# CH32L103-WUI-R1.net
KiCad netlist of a schematic drawn in Altium Designer
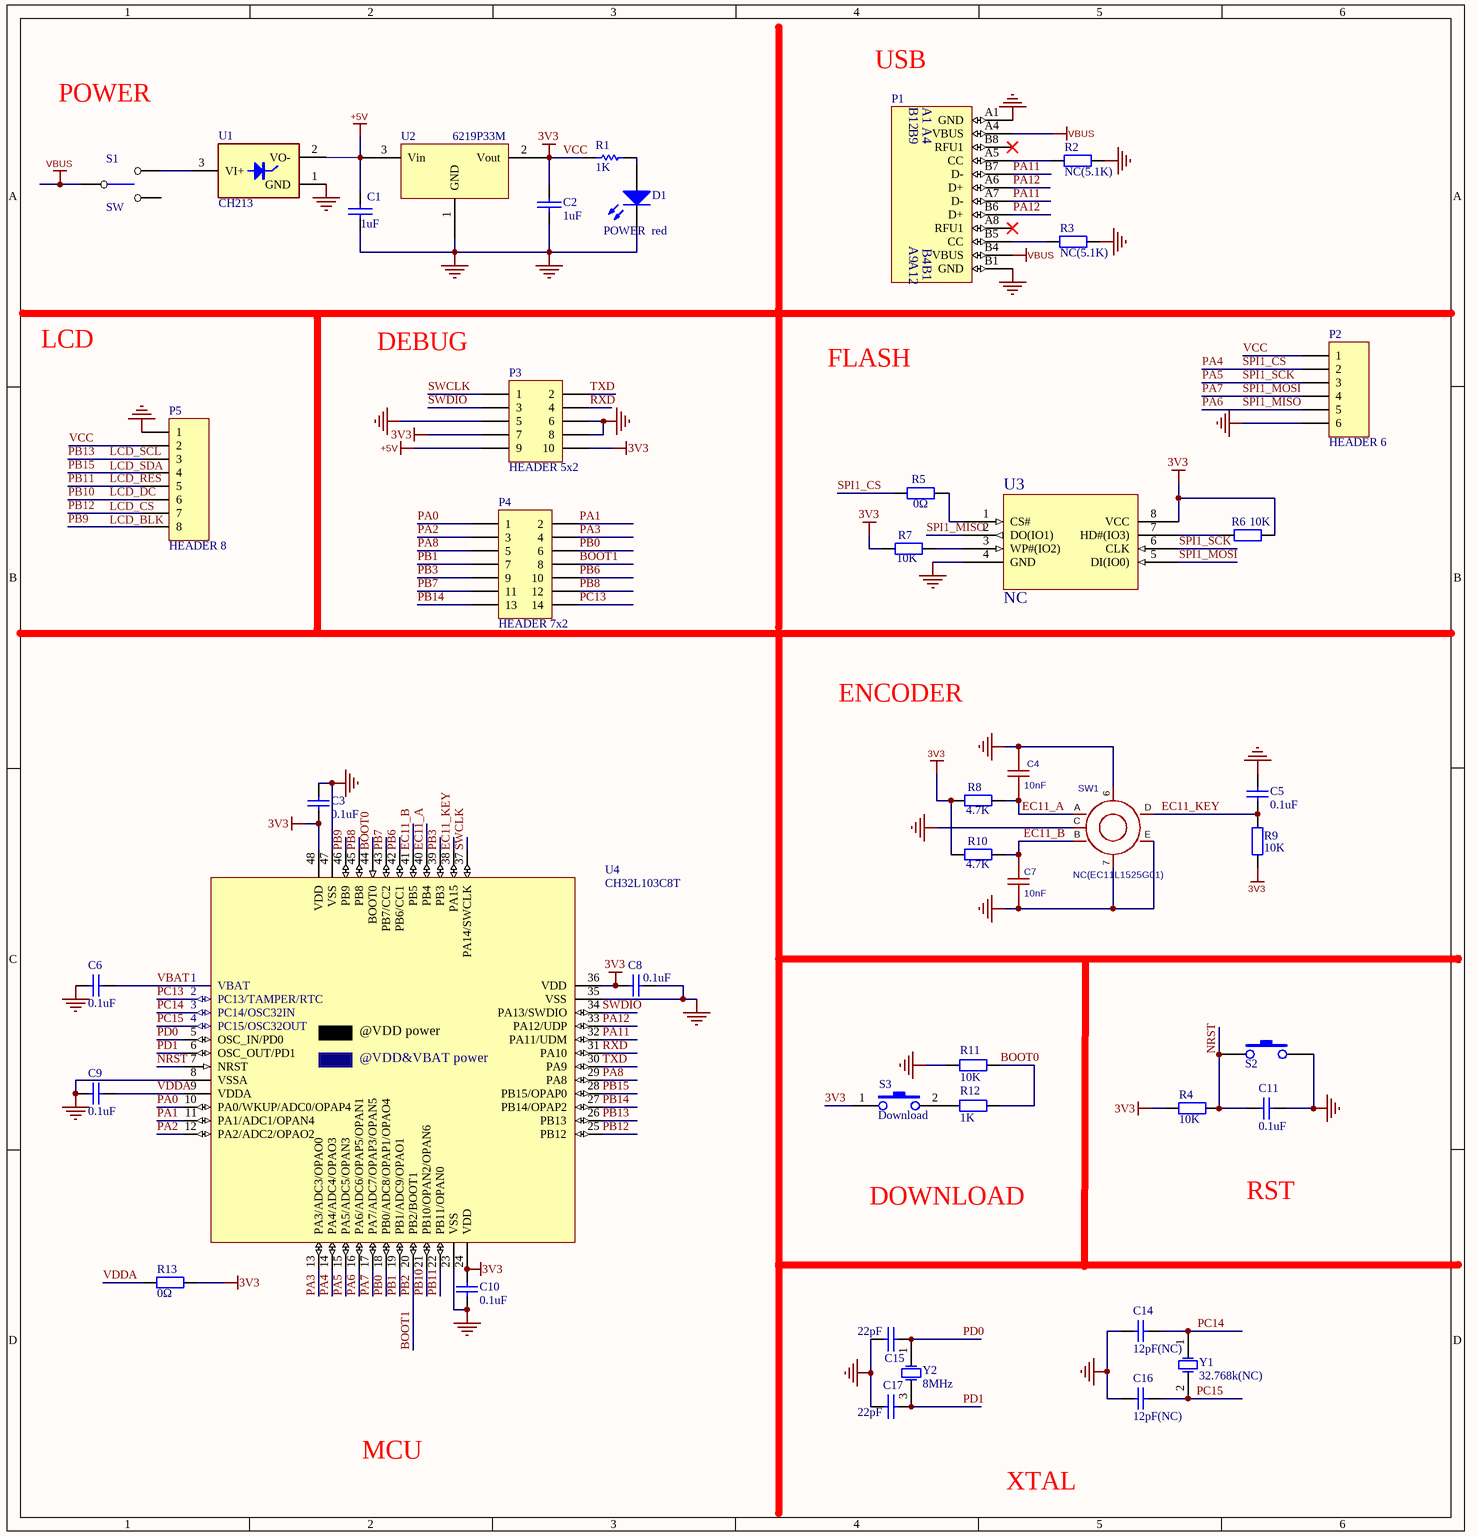
[diagram p0: CH32L103-WUI-R1.SchDoc]

(export (version "E")
  (design (tool "Eeschema 10.0.6"))
  (components
    (comp (ref "C1")
      (value "1uF")
      (footprint "0402_C")
      (description "Capacitor")
      (libsource (lib "*") (part "CAP"))
    )
    (comp (ref "C2")
      (value "1uF")
      (footprint "0402_C")
      (description "Capacitor")
      (libsource (lib "*") (part "CAP"))
    )
    (comp (ref "C3")
      (value "0.1uF")
      (footprint "0402_C")
      (description "Capacitor")
      (fields (field (name "PUBLISHER") "Altium Limited"))
      (libsource (lib "*") (part "Cap"))
    )
    (comp (ref "C4")
      (value "10nF")
      (footprint "0402_C")
      (libsource (lib "altium-import") (part "root_1_CAP_0603_"))
    )
    (comp (ref "C5")
      (value "0.1uF")
      (footprint "0402_C")
      (description "Capacitor")
      (fields (field (name "PUBLISHER") "Altium Limited"))
      (libsource (lib "*") (part "Cap"))
    )
    (comp (ref "C6")
      (value "0.1uF")
      (footprint "0402_C")
      (description "Capacitor")
      (fields (field (name "PUBLISHER") "Altium Limited"))
      (libsource (lib "*") (part "Cap"))
    )
    (comp (ref "C7")
      (value "10nF")
      (footprint "0402_C")
      (libsource (lib "altium-import") (part "root_3_CAP_0603_"))
    )
    (comp (ref "C8")
      (value "0.1uF")
      (footprint "0402_C")
      (description "Capacitor")
      (fields (field (name "PUBLISHER") "Altium Limited"))
      (libsource (lib "*") (part "Cap"))
    )
    (comp (ref "C9")
      (value "0.1uF")
      (footprint "0402_C")
      (description "Capacitor")
      (fields (field (name "PUBLISHER") "Altium Limited"))
      (libsource (lib "*") (part "Cap"))
    )
    (comp (ref "C10")
      (value "0.1uF")
      (footprint "0402_C")
      (description "Capacitor")
      (fields (field (name "PUBLISHER") "Altium Limited"))
      (libsource (lib "*") (part "Cap"))
    )
    (comp (ref "C11")
      (value "0.1uF")
      (footprint "0402_C")
      (description "Capacitor")
      (fields (field (name "PUBLISHER") "Altium Limited"))
      (libsource (lib "*") (part "Cap"))
    )
    (comp (ref "C14")
      (value "12pF(NC)")
      (footprint "0402_C")
      (description "Capacitor")
      (fields (field (name "PUBLISHER") "Altium Limited"))
      (libsource (lib "*") (part "Cap"))
    )
    (comp (ref "C15")
      (value "22pF")
      (footprint "0402_C")
      (description "Capacitor")
      (libsource (lib "*") (part "CAP"))
    )
    (comp (ref "C16")
      (value "12pF(NC)")
      (footprint "0402_C")
      (description "Capacitor")
      (fields (field (name "PUBLISHER") "Altium Limited"))
      (libsource (lib "*") (part "Cap"))
    )
    (comp (ref "C17")
      (value "22pF")
      (footprint "0402_C")
      (description "Capacitor")
      (libsource (lib "*") (part "CAP"))
    )
    (comp (ref "D1")
      (value "POWER  red")
      (footprint "0603+")
      (description "Typical INFRARED GaAs LED")
      (fields (field (name "PUBLISHER") "Altium Limited"))
      (libsource (lib "*") (part "LED0"))
    )
    (comp (ref "P1")
      (value "TYPE-C")
      (footprint "TYPE-C-Receptacle-2.0")
      (libsource (lib "*") (part "TYPE-C1"))
    )
    (comp (ref "P2")
      (value "HEADER 6")
      (footprint "SIP6-2.54mm")
      (description "Header, 6-Pin")
      (libsource (lib "wch_sch_others") (part "HEADER 6"))
    )
    (comp (ref "P3")
      (value "HEADER 5x2")
      (footprint "MYPCB:IDC10-2.54mm")
      (description "Header, 5-Pin, Dual row")
      (libsource (lib "wch_sch_others") (part "HEADER 5x2"))
    )
    (comp (ref "P4")
      (value "HEADER 7x2")
      (footprint "MYPCB:IDC14-2.54mm")
      (description "Header, 7-Pin, Dual row")
      (libsource (lib "wch_sch_others") (part "HEADER 7x2"))
    )
    (comp (ref "P5")
      (value "HEADER 8")
      (footprint "SIP8-2.54mm")
      (description "Header, 8-Pin")
      (libsource (lib "wch_sch_others") (part "HEADER 8"))
    )
    (comp (ref "R1")
      (value "1K")
      (footprint "0402")
      (description "Semiconductor Resistor")
      (fields (field (name "PUBLISHER") "Altium Limited"))
      (libsource (lib "*") (part "Res Semi"))
    )
    (comp (ref "R2")
      (value "NC(5.1K)")
      (footprint "0402")
      (description "Resistor")
      (libsource (lib "Miscellaneous Devices") (part "Res2"))
    )
    (comp (ref "R3")
      (value "NC(5.1K)")
      (footprint "0402")
      (description "Resistor")
      (libsource (lib "Miscellaneous Devices") (part "Res2"))
    )
    (comp (ref "R4")
      (value "10K")
      (footprint "0402")
      (description "Resistor")
      (fields (field (name "PUBLISHER") "Altium Limited"))
      (libsource (lib "") (part "Res2_1"))
    )
    (comp (ref "R5")
      (value "0Ω")
      (footprint "0402")
      (description "Resistor")
      (fields (field (name "PUBLISHER") "Altium Limited"))
      (libsource (lib "*") (part "Res2"))
    )
    (comp (ref "R6")
      (value "10K")
      (footprint "0402")
      (description "Resistor")
      (fields (field (name "PUBLISHER") "Altium Limited"))
      (libsource (lib "*") (part "Res2"))
    )
    (comp (ref "R7")
      (value "10K")
      (footprint "0402")
      (description "Resistor")
      (fields (field (name "PUBLISHER") "Altium Limited"))
      (libsource (lib "*") (part "Res2"))
    )
    (comp (ref "R8")
      (value "4.7K")
      (footprint "0402")
      (description "Resistor")
      (fields (field (name "PUBLISHER") "Altium Limited"))
      (libsource (lib "*") (part "Res2"))
    )
    (comp (ref "R9")
      (value "10K")
      (footprint "0402")
      (description "Resistor")
      (fields (field (name "PUBLISHER") "Altium Limited"))
      (libsource (lib "") (part "Res2_2"))
    )
    (comp (ref "R10")
      (value "4.7K")
      (footprint "0402")
      (description "Resistor")
      (fields (field (name "PUBLISHER") "Altium Limited"))
      (libsource (lib "*") (part "Res2"))
    )
    (comp (ref "R11")
      (value "10K")
      (footprint "0402")
      (description "Resistor")
      (fields (field (name "PUBLISHER") "Altium Limited"))
      (libsource (lib "") (part "Res2_1"))
    )
    (comp (ref "R12")
      (value "1K")
      (footprint "0402")
      (description "Resistor")
      (fields (field (name "PUBLISHER") "Altium Limited"))
      (libsource (lib "") (part "Res2_1"))
    )
    (comp (ref "R13")
      (value "0Ω")
      (footprint "0402")
      (description "Resistor")
      (fields (field (name "PUBLISHER") "Altium Limited"))
      (libsource (lib "") (part "Res2_1"))
    )
    (comp (ref "S1") (value "SW") (footprint "SW1") (libsource (lib "*") (part "SW")))
    (comp (ref "S2") (value "NRST") (footprint "贴片按键") (libsource (lib "*") (part "KEY")))
    (comp (ref "S3") (value "Download") (footprint "贴片按键") (libsource (lib "wch_sch_others") (part "KEY1")))
    (comp (ref "SW1")
      (value "NC(EC11L1525G01)")
      (footprint "SW-TH_ALPS_EC11L1525G01")
      (fields
        (field (name "MANUFACTURER") "ALPSALPINE(阿尔卑斯阿尔派)")
        (field (name "MANUFACTURERPART") "EC11L1525G01")
      )
      (libsource (lib "altium-import") (part "root_3_EC11L1525G01_"))
    )
    (comp (ref "U1")
      (value "CH213")
      (footprint "SOT-23-3")
      (description "Ideal Diode 5V*1A")
      (libsource (lib "CHXXX") (part "CH213E"))
    )
    (comp (ref "U2")
      (value "6219P33M")
      (footprint "SOT-23")
      (libsource (lib "wch_sch_others") (part "6219P33M"))
    )
    (comp (ref "U3")
      (value "NC")
      (footprint "SOIC-8_208mil")
      (libsource (lib "wch_sch_others") (part "W25Q32JV"))
    )
    (comp (ref "U4")
      (value "CH32L103C8T")
      (footprint "LQFP48")
      (description "RISC-V LMD-MCU, 96MHz, USB, Type-C/PD, CAN, OPA, lower power")
      (libsource (lib "CHXXX") (part "CH32L103C8T"))
    )
    (comp (ref "Y1")
      (value "32.768k(NC)")
      (footprint "FC-135")
      (description "Crystal Oscillator")
      (fields (field (name "PUBLISHER") "Altium Limited"))
      (libsource (lib "") (part "XTAL_1"))
    )
    (comp (ref "Y2")
      (value "8MHz")
      (footprint "XT3225")
      (description "Crystal Oscillator")
      (fields (field (name "PUBLISHER") "Altium Limited"))
      (libsource (lib "*") (part "XTAL"))
    )
  )
  (nets
    (net (code "1") (name "+5V") (class "Default")
      (node (ref "C1") (pin "1") (pinfunction "1_1") (pintype "passive"))
      (node (ref "P3") (pin "9") (pinfunction "9_9") (pintype "passive"))
      (node (ref "U1") (pin "2") (pinfunction "VO-_2") (pintype "power_in"))
      (node (ref "U2") (pin "3") (pinfunction "Vin_3") (pintype "passive"))
    )
    (net (code "2") (name "/BOOT0") (class "Default")
      (node (ref "R11") (pin "1") (pinfunction "1_1") (pintype "passive"))
      (node (ref "R12") (pin "1") (pinfunction "1_1") (pintype "passive"))
      (node (ref "U4") (pin "44") (pinfunction "BOOT0_44") (pintype "input"))
    )
    (net (code "3") (name "/BOOT1") (class "Default")
      (node (ref "P4") (pin "8") (pinfunction "8_8") (pintype "passive"))
      (node (ref "U4") (pin "20") (pinfunction "PB2/BOOT1_20") (pintype "bidirectional"))
    )
    (net (code "4") (name "/EC11_A") (class "Default")
      (node (ref "C4") (pin "1") (pinfunction "1_1") (pintype "passive"))
      (node (ref "R8") (pin "2") (pinfunction "2_2") (pintype "passive"))
      (node (ref "SW1") (pin "A") (pinfunction "A_A") (pintype "passive"))
      (node (ref "U4") (pin "40") (pinfunction "PB4_40") (pintype "bidirectional"))
    )
    (net (code "5") (name "/EC11_B") (class "Default")
      (node (ref "C7") (pin "1") (pinfunction "1_1") (pintype "passive"))
      (node (ref "R10") (pin "2") (pinfunction "2_2") (pintype "passive"))
      (node (ref "SW1") (pin "B") (pinfunction "B_B") (pintype "passive"))
      (node (ref "U4") (pin "41") (pinfunction "PB5_41") (pintype "bidirectional"))
    )
    (net (code "6") (name "/EC11_KEY") (class "Default")
      (node (ref "C5") (pin "2") (pinfunction "2_2") (pintype "passive"))
      (node (ref "R9") (pin "2") (pinfunction "2_2") (pintype "passive"))
      (node (ref "SW1") (pin "D") (pinfunction "D_D") (pintype "passive"))
      (node (ref "U4") (pin "38") (pinfunction "PA15_38") (pintype "bidirectional"))
    )
    (net (code "9") (name "/LCD_DC") (class "Default")
      (node (ref "P5") (pin "6") (pinfunction "6_6") (pintype "passive"))
      (node (ref "U4") (pin "21") (pinfunction "PB10/OPAN2/OPAN6_21") (pintype "bidirectional"))
    )
    (net (code "10") (name "/LCD_RES") (class "Default")
      (node (ref "P5") (pin "5") (pinfunction "5_5") (pintype "passive"))
      (node (ref "U4") (pin "22") (pinfunction "PB11/OPAN0_22") (pintype "bidirectional"))
    )
    (net (code "11") (name "/LCD_SCL") (class "Default")
      (node (ref "P5") (pin "3") (pinfunction "3_3") (pintype "passive"))
      (node (ref "U4") (pin "26") (pinfunction "PB13_26") (pintype "bidirectional"))
    )
    (net (code "13") (name "/NRST") (class "Default")
      (node (ref "C11") (pin "2") (pinfunction "2_2") (pintype "passive"))
      (node (ref "R4") (pin "1") (pinfunction "1_1") (pintype "passive"))
      (node (ref "S2") (pin "1") (pinfunction "1_1") (pintype "passive"))
      (node (ref "U4") (pin "7") (pinfunction "NRST_7") (pintype "input"))
    )
    (net (code "14") (name "/PA0") (class "Default")
      (node (ref "P4") (pin "1") (pinfunction "1_1") (pintype "passive"))
      (node (ref "U4") (pin "10") (pinfunction "PA0/WKUP/ADC0/OPAP4_10") (pintype "bidirectional"))
    )
    (net (code "15") (name "/PA1") (class "Default")
      (node (ref "P4") (pin "2") (pinfunction "2_2") (pintype "passive"))
      (node (ref "U4") (pin "11") (pinfunction "PA1/ADC1/OPAN4_11") (pintype "bidirectional"))
    )
    (net (code "16") (name "/PA2") (class "Default")
      (node (ref "P4") (pin "3") (pinfunction "3_3") (pintype "passive"))
      (node (ref "U4") (pin "12") (pinfunction "PA2/ADC2/OPAO2_12") (pintype "bidirectional"))
    )
    (net (code "17") (name "/PA3") (class "Default")
      (node (ref "P4") (pin "4") (pinfunction "4_4") (pintype "passive"))
      (node (ref "U4") (pin "13") (pinfunction "PA3/ADC3/OPAO0_13") (pintype "bidirectional"))
    )
    (net (code "18") (name "/PA4") (class "Default")
      (node (ref "P2") (pin "2") (pinfunction "2_2") (pintype "passive"))
      (node (ref "R5") (pin "1") (pinfunction "1_1") (pintype "passive"))
      (node (ref "U4") (pin "14") (pinfunction "PA4/ADC4/OPAO3_14") (pintype "bidirectional"))
    )
    (net (code "19") (name "/PA5") (class "Default")
      (node (ref "P2") (pin "3") (pinfunction "3_3") (pintype "passive"))
      (node (ref "U3") (pin "6") (pinfunction "CLK_6") (pintype "input"))
      (node (ref "U4") (pin "15") (pinfunction "PA5/ADC5/OPAN3_15") (pintype "bidirectional"))
    )
    (net (code "20") (name "/PA6") (class "Default")
      (node (ref "P2") (pin "5") (pinfunction "5_5") (pintype "passive"))
      (node (ref "U3") (pin "2") (pinfunction "DO(IO1)_2") (pintype "output"))
      (node (ref "U4") (pin "16") (pinfunction "PA6/ADC6/OPAP5/OPAN1_16") (pintype "bidirectional"))
    )
    (net (code "21") (name "/PA7") (class "Default")
      (node (ref "P2") (pin "4") (pinfunction "4_4") (pintype "passive"))
      (node (ref "U3") (pin "5") (pinfunction "DI(IO0)_5") (pintype "input"))
      (node (ref "U4") (pin "17") (pinfunction "PA7/ADC7/OPAP3/OPAN5_17") (pintype "bidirectional"))
    )
    (net (code "22") (name "/PA8") (class "Default")
      (node (ref "P4") (pin "5") (pinfunction "5_5") (pintype "passive"))
      (node (ref "U4") (pin "29") (pinfunction "PA8_29") (pintype "bidirectional"))
    )
    (net (code "23") (name "/PA11") (class "Default")
      (node (ref "P1") (pin "A7") (pinfunction "D-_A7") (pintype "bidirectional"))
      (node (ref "P1") (pin "B7") (pinfunction "D-_B7") (pintype "bidirectional"))
      (node (ref "U4") (pin "32") (pinfunction "PA11/UDM_32") (pintype "bidirectional"))
    )
    (net (code "24") (name "/PA12") (class "Default")
      (node (ref "P1") (pin "A6") (pinfunction "D+_A6") (pintype "bidirectional"))
      (node (ref "P1") (pin "B6") (pinfunction "D+_B6") (pintype "bidirectional"))
      (node (ref "U4") (pin "33") (pinfunction "PA12/UDP_33") (pintype "bidirectional"))
    )
    (net (code "25") (name "/PB0") (class "Default")
      (node (ref "P4") (pin "6") (pinfunction "6_6") (pintype "passive"))
      (node (ref "U4") (pin "18") (pinfunction "PB0/ADC8/OPAP1/OPAO4_18") (pintype "bidirectional"))
    )
    (net (code "26") (name "/PB1") (class "Default")
      (node (ref "P4") (pin "7") (pinfunction "7_7") (pintype "passive"))
      (node (ref "U4") (pin "19") (pinfunction "PB1/ADC9/OPAO1_19") (pintype "bidirectional"))
    )
    (net (code "27") (name "/PB3") (class "Default")
      (node (ref "P4") (pin "9") (pinfunction "9_9") (pintype "passive"))
      (node (ref "U4") (pin "39") (pinfunction "PB3_39") (pintype "bidirectional"))
    )
    (net (code "28") (name "/PB6") (class "Default")
      (node (ref "P4") (pin "10") (pinfunction "10_10") (pintype "passive"))
      (node (ref "U4") (pin "42") (pinfunction "PB6/CC1_42") (pintype "bidirectional"))
    )
    (net (code "29") (name "/PB7") (class "Default")
      (node (ref "P4") (pin "11") (pinfunction "11_11") (pintype "passive"))
      (node (ref "U4") (pin "43") (pinfunction "PB7/CC2_43") (pintype "bidirectional"))
    )
    (net (code "30") (name "/PB8") (class "Default")
      (node (ref "P4") (pin "12") (pinfunction "12_12") (pintype "passive"))
      (node (ref "U4") (pin "45") (pinfunction "PB8_45") (pintype "bidirectional"))
    )
    (net (code "31") (name "/PB9") (class "Default")
      (node (ref "P5") (pin "8") (pinfunction "8_8") (pintype "passive"))
      (node (ref "U4") (pin "46") (pinfunction "PB9_46") (pintype "bidirectional"))
    )
    (net (code "32") (name "/PB12") (class "Default")
      (node (ref "P5") (pin "7") (pinfunction "7_7") (pintype "passive"))
      (node (ref "U4") (pin "25") (pinfunction "PB12_25") (pintype "bidirectional"))
    )
    (net (code "33") (name "/PB14") (class "Default")
      (node (ref "P4") (pin "13") (pinfunction "13_13") (pintype "passive"))
      (node (ref "U4") (pin "27") (pinfunction "PB14/OPAP2_27") (pintype "bidirectional"))
    )
    (net (code "34") (name "/PB15") (class "Default")
      (node (ref "P5") (pin "4") (pinfunction "4_4") (pintype "passive"))
      (node (ref "U4") (pin "28") (pinfunction "PB15/OPAP0_28") (pintype "bidirectional"))
    )
    (net (code "35") (name "/PC13") (class "Default")
      (node (ref "P4") (pin "14") (pinfunction "14_14") (pintype "passive"))
      (node (ref "U4") (pin "2") (pinfunction "PC13/TAMPER/RTC_2") (pintype "bidirectional"))
    )
    (net (code "36") (name "/PC14") (class "Default")
      (node (ref "C14") (pin "1") (pinfunction "1_1") (pintype "passive"))
      (node (ref "U4") (pin "3") (pinfunction "PC14/OSC32IN_3") (pintype "bidirectional"))
      (node (ref "Y1") (pin "1") (pinfunction "OSC1_1") (pintype "passive"))
    )
    (net (code "37") (name "/PC15") (class "Default")
      (node (ref "C16") (pin "1") (pinfunction "1_1") (pintype "passive"))
      (node (ref "U4") (pin "4") (pinfunction "PC15/OSC32OUT_4") (pintype "bidirectional"))
      (node (ref "Y1") (pin "2") (pinfunction "OSC2_2") (pintype "passive"))
    )
    (net (code "38") (name "/PD0") (class "Default")
      (node (ref "C15") (pin "2") (pinfunction "2_2") (pintype "passive"))
      (node (ref "U4") (pin "5") (pinfunction "OSC_IN/PD0_5") (pintype "bidirectional"))
      (node (ref "Y2") (pin "1") (pinfunction "OSC1_1") (pintype "passive"))
    )
    (net (code "39") (name "/PD1") (class "Default")
      (node (ref "C17") (pin "2") (pinfunction "2_2") (pintype "passive"))
      (node (ref "U4") (pin "6") (pinfunction "OSC_OUT/PD1_6") (pintype "bidirectional"))
      (node (ref "Y2") (pin "3") (pinfunction "OSC2_3") (pintype "passive"))
    )
    (net (code "40") (name "/RXD") (class "Default")
      (node (ref "P3") (pin "4") (pinfunction "4_4") (pintype "passive"))
      (node (ref "U4") (pin "31") (pinfunction "PA10_31") (pintype "bidirectional"))
    )
    (net (code "41") (name "/SWCLK") (class "Default")
      (node (ref "P3") (pin "1") (pinfunction "1_1") (pintype "passive"))
      (node (ref "U4") (pin "37") (pinfunction "PA14/SWCLK_37") (pintype "bidirectional"))
    )
    (net (code "42") (name "/SWDIO") (class "Default")
      (node (ref "P3") (pin "3") (pinfunction "3_3") (pintype "passive"))
      (node (ref "U4") (pin "34") (pinfunction "PA13/SWDIO_34") (pintype "bidirectional"))
    )
    (net (code "43") (name "/TXD") (class "Default")
      (node (ref "P3") (pin "2") (pinfunction "2_2") (pintype "passive"))
      (node (ref "U4") (pin "30") (pinfunction "PA9_30") (pintype "bidirectional"))
    )
    (net (code "44") (name "/VBAT") (class "Default")
      (node (ref "C6") (pin "1") (pinfunction "1_1") (pintype "passive"))
      (node (ref "U4") (pin "1") (pinfunction "VBAT_1") (pintype "power_in"))
    )
    (net (code "45") (name "/VDDA") (class "Default")
      (node (ref "C9") (pin "1") (pinfunction "1_1") (pintype "passive"))
      (node (ref "R13") (pin "2") (pinfunction "2_2") (pintype "passive"))
      (node (ref "U4") (pin "9") (pinfunction "VDDA_9") (pintype "power_in"))
    )
    (net (code "46") (name "3V3") (class "Default")
      (node (ref "C10") (pin "2") (pinfunction "2_2") (pintype "passive"))
      (node (ref "C2") (pin "1") (pinfunction "1_1") (pintype "passive"))
      (node (ref "C3") (pin "2") (pinfunction "2_2") (pintype "passive"))
      (node (ref "C8") (pin "2") (pinfunction "2_2") (pintype "passive"))
      (node (ref "P2") (pin "1") (pinfunction "1_1") (pintype "passive"))
      (node (ref "P3") (pin "10") (pinfunction "10_10") (pintype "passive"))
      (node (ref "P3") (pin "7") (pinfunction "7_7") (pintype "passive"))
      (node (ref "P5") (pin "2") (pinfunction "2_2") (pintype "passive"))
      (node (ref "R1") (pin "2") (pinfunction "2_2") (pintype "passive"))
      (node (ref "R10") (pin "1") (pinfunction "1_1") (pintype "passive"))
      (node (ref "R13") (pin "1") (pinfunction "1_1") (pintype "passive"))
      (node (ref "R4") (pin "2") (pinfunction "2_2") (pintype "passive"))
      (node (ref "R6") (pin "2") (pinfunction "2_2") (pintype "passive"))
      (node (ref "R7") (pin "1") (pinfunction "1_1") (pintype "passive"))
      (node (ref "R8") (pin "1") (pinfunction "1_1") (pintype "passive"))
      (node (ref "R9") (pin "1") (pinfunction "1_1") (pintype "passive"))
      (node (ref "S3") (pin "1") (pinfunction "1_1") (pintype "passive"))
      (node (ref "U2") (pin "2") (pinfunction "Vout_2") (pintype "passive"))
      (node (ref "U3") (pin "8") (pinfunction "VCC_8") (pintype "power_in"))
      (node (ref "U4") (pin "24") (pinfunction "VDD_24") (pintype "power_in"))
      (node (ref "U4") (pin "36") (pinfunction "VDD_36") (pintype "power_in"))
      (node (ref "U4") (pin "48") (pinfunction "VDD_48") (pintype "power_in"))
    )
    (net (code "47") (name "GND") (class "Default")
      (node (ref "C1") (pin "2") (pinfunction "2_2") (pintype "passive"))
      (node (ref "C10") (pin "1") (pinfunction "1_1") (pintype "passive"))
      (node (ref "C11") (pin "1") (pinfunction "1_1") (pintype "passive"))
      (node (ref "C14") (pin "2") (pinfunction "2_2") (pintype "passive"))
      (node (ref "C15") (pin "1") (pinfunction "1_1") (pintype "passive"))
      (node (ref "C16") (pin "2") (pinfunction "2_2") (pintype "passive"))
      (node (ref "C17") (pin "1") (pinfunction "1_1") (pintype "passive"))
      (node (ref "C2") (pin "2") (pinfunction "2_2") (pintype "passive"))
      (node (ref "C3") (pin "1") (pinfunction "1_1") (pintype "passive"))
      (node (ref "C4") (pin "2") (pinfunction "2_2") (pintype "passive"))
      (node (ref "C5") (pin "1") (pinfunction "1_1") (pintype "passive"))
      (node (ref "C6") (pin "2") (pinfunction "2_2") (pintype "passive"))
      (node (ref "C7") (pin "2") (pinfunction "2_2") (pintype "passive"))
      (node (ref "C8") (pin "1") (pinfunction "1_1") (pintype "passive"))
      (node (ref "C9") (pin "2") (pinfunction "2_2") (pintype "passive"))
      (node (ref "D1") (pin "2") (pinfunction "K_2") (pintype "passive"))
      (node (ref "P1") (pin "A1") (pinfunction "GND_A1") (pintype "bidirectional"))
      (node (ref "P1") (pin "B1") (pinfunction "GND_B1") (pintype "bidirectional"))
      (node (ref "P2") (pin "6") (pinfunction "6_6") (pintype "passive"))
      (node (ref "P3") (pin "5") (pinfunction "5_5") (pintype "passive"))
      (node (ref "P3") (pin "6") (pinfunction "6_6") (pintype "passive"))
      (node (ref "P3") (pin "8") (pinfunction "8_8") (pintype "passive"))
      (node (ref "P5") (pin "1") (pinfunction "1_1") (pintype "passive"))
      (node (ref "R11") (pin "2") (pinfunction "2_2") (pintype "passive"))
      (node (ref "R2") (pin "2") (pinfunction "2_2") (pintype "passive"))
      (node (ref "R3") (pin "2") (pinfunction "2_2") (pintype "passive"))
      (node (ref "S2") (pin "2") (pinfunction "2_2") (pintype "passive"))
      (node (ref "SW1") (pin "6") (pinfunction "EH_6") (pintype "passive"))
      (node (ref "SW1") (pin "7") (pinfunction "EH_7") (pintype "passive"))
      (node (ref "SW1") (pin "C") (pinfunction "C_C") (pintype "passive"))
      (node (ref "SW1") (pin "E") (pinfunction "E_E") (pintype "passive"))
      (node (ref "U1") (pin "1") (pinfunction "GND_1") (pintype "power_in"))
      (node (ref "U2") (pin "1") (pinfunction "GND_1") (pintype "passive"))
      (node (ref "U3") (pin "4") (pinfunction "GND_4") (pintype "power_in"))
      (node (ref "U4") (pin "23") (pinfunction "VSS_23") (pintype "power_in"))
      (node (ref "U4") (pin "35") (pinfunction "VSS_35") (pintype "power_in"))
      (node (ref "U4") (pin "47") (pinfunction "VSS_47") (pintype "power_in"))
      (node (ref "U4") (pin "8") (pinfunction "VSSA_8") (pintype "power_in"))
    )
    (net (code "48") (name "Net-(D1-A)") (class "Default")
      (node (ref "D1") (pin "1") (pinfunction "A_1") (pintype "passive"))
      (node (ref "R1") (pin "1") (pinfunction "1_1") (pintype "passive"))
    )
    (net (code "49") (name "Net-(P1-CC-PadA5)") (class "Default")
      (node (ref "P1") (pin "A5") (pinfunction "CC_A5") (pintype "bidirectional"))
      (node (ref "R2") (pin "1") (pinfunction "1_1") (pintype "passive"))
    )
    (net (code "50") (name "Net-(P1-CC-PadB5)") (class "Default")
      (node (ref "P1") (pin "B5") (pinfunction "CC_B5") (pintype "bidirectional"))
      (node (ref "R3") (pin "1") (pinfunction "1_1") (pintype "passive"))
    )
    (net (code "51") (name "Net-(R12-Pad2)") (class "Default")
      (node (ref "R12") (pin "2") (pinfunction "2_2") (pintype "passive"))
      (node (ref "S3") (pin "2") (pinfunction "2_2") (pintype "passive"))
    )
    (net (code "52") (name "Net-(U1-VI+)") (class "Default")
      (node (ref "S1") (pin "3") (pinfunction "3_3") (pintype "passive"))
      (node (ref "U1") (pin "3") (pinfunction "VI+_3") (pintype "power_in"))
    )
    (net (code "53") (name "Net-(U3-CS#)") (class "Default")
      (node (ref "R5") (pin "2") (pinfunction "2_2") (pintype "passive"))
      (node (ref "U3") (pin "1") (pinfunction "CS#_1") (pintype "input"))
    )
    (net (code "54") (name "Net-(U3-HD#(IO3))") (class "Default")
      (node (ref "R6") (pin "1") (pinfunction "1_1") (pintype "passive"))
      (node (ref "U3") (pin "7") (pinfunction "HD#(IO3)_7") (pintype "power_in"))
    )
    (net (code "55") (name "Net-(U3-WP#(IO2))") (class "Default")
      (node (ref "R7") (pin "2") (pinfunction "2_2") (pintype "passive"))
      (node (ref "U3") (pin "3") (pinfunction "WP#(IO2)_3") (pintype "input"))
    )
    (net (code "56") (name "VBUS") (class "Default")
      (node (ref "P1") (pin "A4") (pinfunction "VBUS_A4") (pintype "bidirectional"))
      (node (ref "P1") (pin "B4") (pinfunction "VBUS_B4") (pintype "bidirectional"))
      (node (ref "S1") (pin "1") (pinfunction "1_1") (pintype "passive"))
    )
    (net (code "57") (name "unconnected-(P1-RFU1-PadA8)") (class "Default")
      (node (ref "P1") (pin "A8") (pinfunction "RFU1_A8") (pintype "bidirectional+no_connect"))
    )
    (net (code "58") (name "unconnected-(P1-RFU1-PadB8)") (class "Default")
      (node (ref "P1") (pin "B8") (pinfunction "RFU1_B8") (pintype "bidirectional+no_connect"))
    )
    (net (code "59") (name "unconnected-(S1-Pad2)") (class "Default")
      (node (ref "S1") (pin "2") (pinfunction "2_2") (pintype "passive"))
    )
  )
)
